# Main_circuit.net
KiCad netlist of a schematic drawn in EAGLE
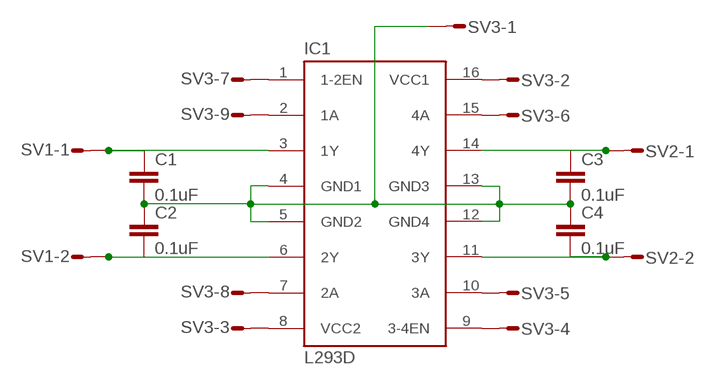
[diagram p0: schematic, sheet 1]

(export (version "E")
  (design (tool "Eeschema 10.0.6"))
  (components
    (comp (ref "C1")
      (value "0.1uF")
      (footprint "eagle-import:C2.5-2")
      (libsource (lib "eagle-import") (part "C2.5/2"))
    )
    (comp (ref "C2")
      (value "0.1uF")
      (footprint "eagle-import:C2.5-2")
      (libsource (lib "eagle-import") (part "C2.5/2"))
    )
    (comp (ref "C3")
      (value "0.1uF")
      (footprint "eagle-import:C2.5-2")
      (libsource (lib "eagle-import") (part "C2.5/2"))
    )
    (comp (ref "C4")
      (value "0.1uF")
      (footprint "eagle-import:C2.5-2")
      (libsource (lib "eagle-import") (part "C2.5/2"))
    )
    (comp (ref "IC1")
      (value "L293D")
      (footprint "eagle-import:DIL16")
      (libsource (lib "eagle-import") (part "L293D"))
    )
    (comp (ref "SV1")
      (value "L02P")
      (footprint "eagle-import:L02P")
      (libsource (lib "eagle-import") (part "L02P"))
    )
    (comp (ref "SV2")
      (value "L02P")
      (footprint "eagle-import:L02P")
      (libsource (lib "eagle-import") (part "L02P"))
    )
    (comp (ref "SV3")
      (value "L09P")
      (footprint "eagle-import:L09P")
      (libsource (lib "eagle-import") (part "L09P"))
    )
  )
  (nets
    (net (code "1") (name "Net-(IC1-1-2EN)") (class "Default")
      (node (ref "IC1") (pin "1") (pinfunction "1-2EN_1") (pintype "input"))
      (node (ref "SV3") (pin "7") (pinfunction "S_7") (pintype "passive"))
    )
    (net (code "2") (name "Net-(IC1-1A)") (class "Default")
      (node (ref "IC1") (pin "2") (pinfunction "1A_2") (pintype "input"))
      (node (ref "SV3") (pin "9") (pinfunction "S_9") (pintype "passive"))
    )
    (net (code "3") (name "Net-(IC1-1Y)") (class "Default")
      (node (ref "C1") (pin "1") (pinfunction "1_1") (pintype "passive"))
      (node (ref "IC1") (pin "3") (pinfunction "1Y_3") (pintype "output"))
      (node (ref "SV1") (pin "1") (pinfunction "S_1") (pintype "passive"))
    )
    (net (code "4") (name "Net-(IC1-2A)") (class "Default")
      (node (ref "IC1") (pin "7") (pinfunction "2A_7") (pintype "input"))
      (node (ref "SV3") (pin "8") (pinfunction "S_8") (pintype "passive"))
    )
    (net (code "5") (name "Net-(IC1-2Y)") (class "Default")
      (node (ref "C2") (pin "2") (pinfunction "2_2") (pintype "passive"))
      (node (ref "IC1") (pin "6") (pinfunction "2Y_6") (pintype "output"))
      (node (ref "SV1") (pin "2") (pinfunction "S_2") (pintype "passive"))
    )
    (net (code "6") (name "Net-(IC1-3-4EN)") (class "Default")
      (node (ref "IC1") (pin "9") (pinfunction "3-4EN_9") (pintype "input"))
      (node (ref "SV3") (pin "4") (pinfunction "S_4") (pintype "passive"))
    )
    (net (code "7") (name "Net-(IC1-3A)") (class "Default")
      (node (ref "IC1") (pin "10") (pinfunction "3A_10") (pintype "input"))
      (node (ref "SV3") (pin "5") (pinfunction "S_5") (pintype "passive"))
    )
    (net (code "8") (name "Net-(IC1-3Y)") (class "Default")
      (node (ref "C4") (pin "2") (pinfunction "2_2") (pintype "passive"))
      (node (ref "IC1") (pin "11") (pinfunction "3Y_11") (pintype "output"))
      (node (ref "SV2") (pin "2") (pinfunction "S_2") (pintype "passive"))
    )
    (net (code "9") (name "Net-(IC1-4A)") (class "Default")
      (node (ref "IC1") (pin "15") (pinfunction "4A_15") (pintype "input"))
      (node (ref "SV3") (pin "6") (pinfunction "S_6") (pintype "passive"))
    )
    (net (code "10") (name "Net-(IC1-4Y)") (class "Default")
      (node (ref "C3") (pin "1") (pinfunction "1_1") (pintype "passive"))
      (node (ref "IC1") (pin "14") (pinfunction "4Y_14") (pintype "output"))
      (node (ref "SV2") (pin "1") (pinfunction "S_1") (pintype "passive"))
    )
    (net (code "11") (name "Net-(IC1-GND1)") (class "Default")
      (node (ref "C1") (pin "2") (pinfunction "2_2") (pintype "passive"))
      (node (ref "C2") (pin "1") (pinfunction "1_1") (pintype "passive"))
      (node (ref "C3") (pin "2") (pinfunction "2_2") (pintype "passive"))
      (node (ref "C4") (pin "1") (pinfunction "1_1") (pintype "passive"))
      (node (ref "IC1") (pin "12") (pinfunction "GND4_12") (pintype "power_in"))
      (node (ref "IC1") (pin "13") (pinfunction "GND3_13") (pintype "power_in"))
      (node (ref "IC1") (pin "4") (pinfunction "GND1_4") (pintype "power_in"))
      (node (ref "IC1") (pin "5") (pinfunction "GND2_5") (pintype "power_in"))
      (node (ref "SV3") (pin "1") (pinfunction "S_1") (pintype "passive"))
    )
    (net (code "12") (name "Net-(IC1-VCC1)") (class "Default")
      (node (ref "IC1") (pin "16") (pinfunction "VCC1_16") (pintype "power_in"))
      (node (ref "SV3") (pin "2") (pinfunction "S_2") (pintype "passive"))
    )
    (net (code "13") (name "Net-(IC1-VCC2)") (class "Default")
      (node (ref "IC1") (pin "8") (pinfunction "VCC2_8") (pintype "power_in"))
      (node (ref "SV3") (pin "3") (pinfunction "S_3") (pintype "passive"))
    )
  )
)
